# 6_ZynTra-Zynq-DDR_Interface.net
KiCad netlist of a schematic drawn in Altium Designer
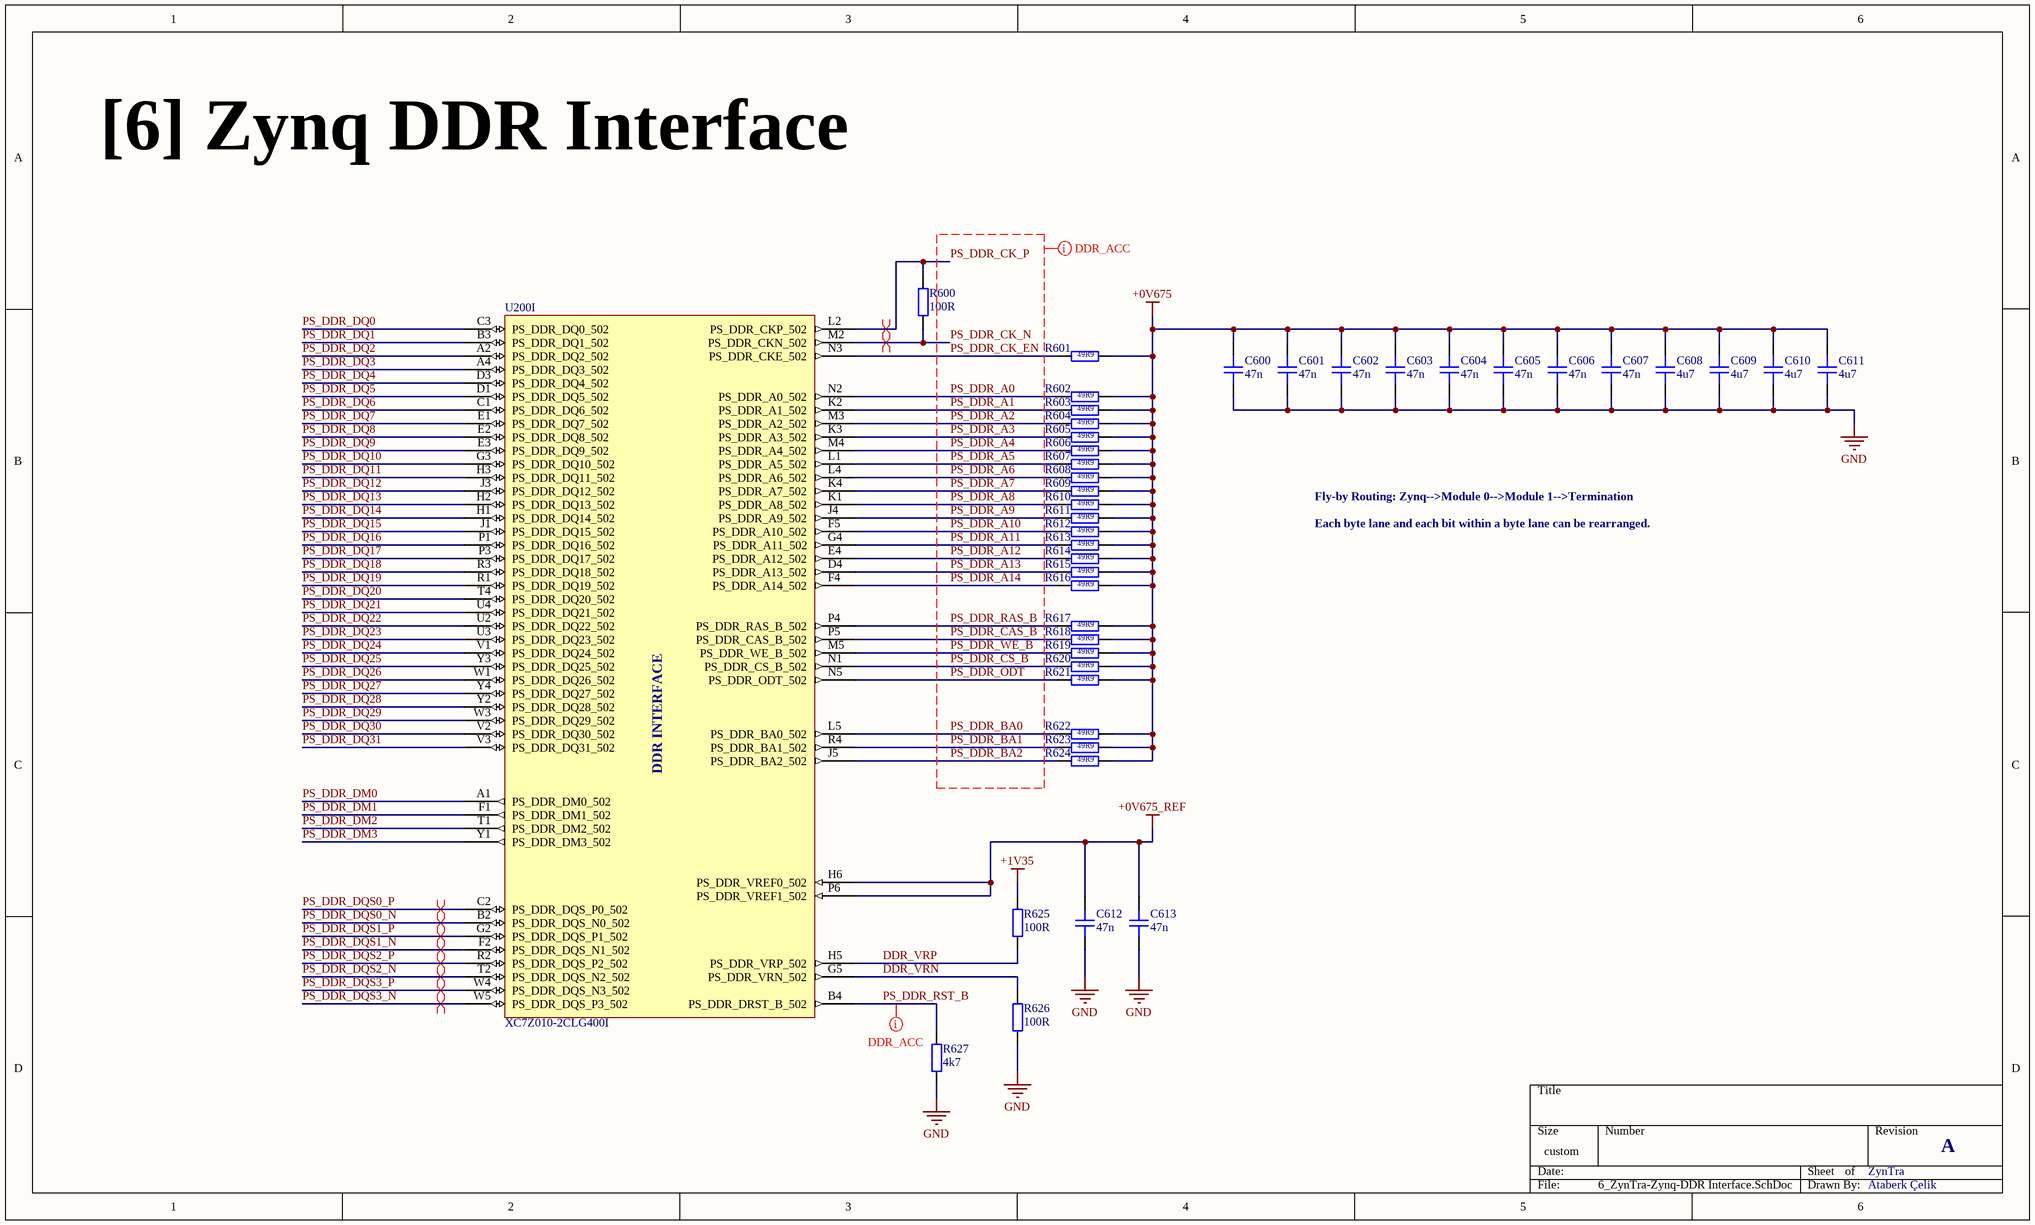
[diagram p0: 6_ZynTra-Zynq-DDR Interface.SchDoc]

(export (version "E")
  (design (tool "Eeschema 10.0.6"))
  (components
    (comp (ref "C600")
      (value "47n")
      (footprint "CAP_0201")
      (description "Capacitor SMD 0201")
      (libsource (lib "Schematic-Lib-PhilsLab") (part "CAP_0201"))
    )
    (comp (ref "C601")
      (value "47n")
      (footprint "CAP_0201")
      (description "Capacitor SMD 0201")
      (libsource (lib "Schematic-Lib-PhilsLab") (part "CAP_0201"))
    )
    (comp (ref "C602")
      (value "47n")
      (footprint "CAP_0201")
      (description "Capacitor SMD 0201")
      (libsource (lib "Schematic-Lib-PhilsLab") (part "CAP_0201"))
    )
    (comp (ref "C603")
      (value "47n")
      (footprint "CAP_0201")
      (description "Capacitor SMD 0201")
      (libsource (lib "Schematic-Lib-PhilsLab") (part "CAP_0201"))
    )
    (comp (ref "C604")
      (value "47n")
      (footprint "CAP_0201")
      (description "Capacitor SMD 0201")
      (libsource (lib "Schematic-Lib-PhilsLab") (part "CAP_0201"))
    )
    (comp (ref "C605")
      (value "47n")
      (footprint "CAP_0201")
      (description "Capacitor SMD 0201")
      (libsource (lib "Schematic-Lib-PhilsLab") (part "CAP_0201"))
    )
    (comp (ref "C606")
      (value "47n")
      (footprint "CAP_0201")
      (description "Capacitor SMD 0201")
      (libsource (lib "Schematic-Lib-PhilsLab") (part "CAP_0201"))
    )
    (comp (ref "C607")
      (value "47n")
      (footprint "CAP_0201")
      (description "Capacitor SMD 0201")
      (libsource (lib "Schematic-Lib-PhilsLab") (part "CAP_0201"))
    )
    (comp (ref "C608")
      (value "4u7")
      (footprint "CAP_0402")
      (description "Capacitor SMD 0402")
      (libsource (lib "Schematic-Lib-PhilsLab") (part "CAP_0402"))
    )
    (comp (ref "C609")
      (value "4u7")
      (footprint "CAP_0402")
      (description "Capacitor SMD 0402")
      (libsource (lib "Schematic-Lib-PhilsLab") (part "CAP_0402"))
    )
    (comp (ref "C610")
      (value "4u7")
      (footprint "CAP_0402")
      (description "Capacitor SMD 0402")
      (libsource (lib "Schematic-Lib-PhilsLab") (part "CAP_0402"))
    )
    (comp (ref "C611")
      (value "4u7")
      (footprint "CAP_0402")
      (description "Capacitor SMD 0402")
      (libsource (lib "Schematic-Lib-PhilsLab") (part "CAP_0402"))
    )
    (comp (ref "C612")
      (value "47n")
      (footprint "CAP_0201")
      (description "Capacitor SMD 0201")
      (libsource (lib "Schematic-Lib-PhilsLab") (part "CAP_0201"))
    )
    (comp (ref "C613")
      (value "47n")
      (footprint "CAP_0201")
      (description "Capacitor SMD 0201")
      (libsource (lib "Schematic-Lib-PhilsLab") (part "CAP_0201"))
    )
    (comp (ref "R600")
      (value "100R")
      (footprint "RES_0201")
      (description "Resistor SMD 0201")
      (libsource (lib "Schematic-Lib-PhilsLab") (part "RES_0201"))
    )
    (comp (ref "R601")
      (value "49R9")
      (footprint "RES_0201")
      (description "Resistor SMD 0201")
      (libsource (lib "Schematic-Lib-PhilsLab") (part "RES_0201"))
    )
    (comp (ref "R602")
      (value "49R9")
      (footprint "RES_0201")
      (description "Resistor SMD 0201")
      (libsource (lib "Schematic-Lib-PhilsLab") (part "RES_0201"))
    )
    (comp (ref "R603")
      (value "49R9")
      (footprint "RES_0201")
      (description "Resistor SMD 0201")
      (libsource (lib "Schematic-Lib-PhilsLab") (part "RES_0201"))
    )
    (comp (ref "R604")
      (value "49R9")
      (footprint "RES_0201")
      (description "Resistor SMD 0201")
      (libsource (lib "Schematic-Lib-PhilsLab") (part "RES_0201"))
    )
    (comp (ref "R605")
      (value "49R9")
      (footprint "RES_0201")
      (description "Resistor SMD 0201")
      (libsource (lib "Schematic-Lib-PhilsLab") (part "RES_0201"))
    )
    (comp (ref "R606")
      (value "49R9")
      (footprint "RES_0201")
      (description "Resistor SMD 0201")
      (libsource (lib "Schematic-Lib-PhilsLab") (part "RES_0201"))
    )
    (comp (ref "R607")
      (value "49R9")
      (footprint "RES_0201")
      (description "Resistor SMD 0201")
      (libsource (lib "Schematic-Lib-PhilsLab") (part "RES_0201"))
    )
    (comp (ref "R608")
      (value "49R9")
      (footprint "RES_0201")
      (description "Resistor SMD 0201")
      (libsource (lib "Schematic-Lib-PhilsLab") (part "RES_0201"))
    )
    (comp (ref "R609")
      (value "49R9")
      (footprint "RES_0201")
      (description "Resistor SMD 0201")
      (libsource (lib "Schematic-Lib-PhilsLab") (part "RES_0201"))
    )
    (comp (ref "R610")
      (value "49R9")
      (footprint "RES_0201")
      (description "Resistor SMD 0201")
      (libsource (lib "Schematic-Lib-PhilsLab") (part "RES_0201"))
    )
    (comp (ref "R611")
      (value "49R9")
      (footprint "RES_0201")
      (description "Resistor SMD 0201")
      (libsource (lib "Schematic-Lib-PhilsLab") (part "RES_0201"))
    )
    (comp (ref "R612")
      (value "49R9")
      (footprint "RES_0201")
      (description "Resistor SMD 0201")
      (libsource (lib "Schematic-Lib-PhilsLab") (part "RES_0201"))
    )
    (comp (ref "R613")
      (value "49R9")
      (footprint "RES_0201")
      (description "Resistor SMD 0201")
      (libsource (lib "Schematic-Lib-PhilsLab") (part "RES_0201"))
    )
    (comp (ref "R614")
      (value "49R9")
      (footprint "RES_0201")
      (description "Resistor SMD 0201")
      (libsource (lib "Schematic-Lib-PhilsLab") (part "RES_0201"))
    )
    (comp (ref "R615")
      (value "49R9")
      (footprint "RES_0201")
      (description "Resistor SMD 0201")
      (libsource (lib "Schematic-Lib-PhilsLab") (part "RES_0201"))
    )
    (comp (ref "R616")
      (value "49R9")
      (footprint "RES_0201")
      (description "Resistor SMD 0201")
      (libsource (lib "Schematic-Lib-PhilsLab") (part "RES_0201"))
    )
    (comp (ref "R617")
      (value "49R9")
      (footprint "RES_0201")
      (description "Resistor SMD 0201")
      (libsource (lib "Schematic-Lib-PhilsLab") (part "RES_0201"))
    )
    (comp (ref "R618")
      (value "49R9")
      (footprint "RES_0201")
      (description "Resistor SMD 0201")
      (libsource (lib "Schematic-Lib-PhilsLab") (part "RES_0201"))
    )
    (comp (ref "R619")
      (value "49R9")
      (footprint "RES_0201")
      (description "Resistor SMD 0201")
      (libsource (lib "Schematic-Lib-PhilsLab") (part "RES_0201"))
    )
    (comp (ref "R620")
      (value "49R9")
      (footprint "RES_0201")
      (description "Resistor SMD 0201")
      (libsource (lib "Schematic-Lib-PhilsLab") (part "RES_0201"))
    )
    (comp (ref "R621")
      (value "49R9")
      (footprint "RES_0201")
      (description "Resistor SMD 0201")
      (libsource (lib "Schematic-Lib-PhilsLab") (part "RES_0201"))
    )
    (comp (ref "R622")
      (value "49R9")
      (footprint "RES_0201")
      (description "Resistor SMD 0201")
      (libsource (lib "Schematic-Lib-PhilsLab") (part "RES_0201"))
    )
    (comp (ref "R623")
      (value "49R9")
      (footprint "RES_0201")
      (description "Resistor SMD 0201")
      (libsource (lib "Schematic-Lib-PhilsLab") (part "RES_0201"))
    )
    (comp (ref "R624")
      (value "49R9")
      (footprint "RES_0201")
      (description "Resistor SMD 0201")
      (libsource (lib "Schematic-Lib-PhilsLab") (part "RES_0201"))
    )
    (comp (ref "R625")
      (value "100R")
      (footprint "RES_0201")
      (description "Resistor SMD 0201")
      (libsource (lib "Schematic-Lib-PhilsLab") (part "RES_0201"))
    )
    (comp (ref "R626")
      (value "100R")
      (footprint "RES_0201")
      (description "Resistor SMD 0201")
      (libsource (lib "Schematic-Lib-PhilsLab") (part "RES_0201"))
    )
    (comp (ref "R627")
      (value "4k7")
      (footprint "RES_0201")
      (description "Resistor SMD 0201")
      (libsource (lib "Schematic-Lib-PhilsLab") (part "RES_0201"))
    )
    (comp (ref "U200")
      (value "XC7Z010-2CLG400I")
      (footprint "CLG400, 0.8mm, 17x17")
      (fields (field (name "MANUFACTURER") "AMD / Xilinx"))
      (libsource (lib "AtaSchLib") (part "XC7Z010-2CLG400I"))
    )
  )
  (nets
    (net (code "1") (name "+0V675") (class "Default")
      (node (ref "C600") (pin "2") (pinfunction "2_2") (pintype "passive"))
      (node (ref "C601") (pin "2") (pinfunction "2_2") (pintype "passive"))
      (node (ref "C602") (pin "2") (pinfunction "2_2") (pintype "passive"))
      (node (ref "C603") (pin "2") (pinfunction "2_2") (pintype "passive"))
      (node (ref "C604") (pin "2") (pinfunction "2_2") (pintype "passive"))
      (node (ref "C605") (pin "2") (pinfunction "2_2") (pintype "passive"))
      (node (ref "C606") (pin "2") (pinfunction "2_2") (pintype "passive"))
      (node (ref "C607") (pin "2") (pinfunction "2_2") (pintype "passive"))
      (node (ref "C608") (pin "2") (pinfunction "2_2") (pintype "passive"))
      (node (ref "C609") (pin "2") (pinfunction "2_2") (pintype "passive"))
      (node (ref "C610") (pin "2") (pinfunction "2_2") (pintype "passive"))
      (node (ref "C611") (pin "2") (pinfunction "2_2") (pintype "passive"))
      (node (ref "R601") (pin "2") (pinfunction "2_2") (pintype "passive"))
      (node (ref "R602") (pin "2") (pinfunction "2_2") (pintype "passive"))
      (node (ref "R603") (pin "2") (pinfunction "2_2") (pintype "passive"))
      (node (ref "R604") (pin "2") (pinfunction "2_2") (pintype "passive"))
      (node (ref "R605") (pin "2") (pinfunction "2_2") (pintype "passive"))
      (node (ref "R606") (pin "2") (pinfunction "2_2") (pintype "passive"))
      (node (ref "R607") (pin "2") (pinfunction "2_2") (pintype "passive"))
      (node (ref "R608") (pin "2") (pinfunction "2_2") (pintype "passive"))
      (node (ref "R609") (pin "2") (pinfunction "2_2") (pintype "passive"))
      (node (ref "R610") (pin "2") (pinfunction "2_2") (pintype "passive"))
      (node (ref "R611") (pin "2") (pinfunction "2_2") (pintype "passive"))
      (node (ref "R612") (pin "2") (pinfunction "2_2") (pintype "passive"))
      (node (ref "R613") (pin "2") (pinfunction "2_2") (pintype "passive"))
      (node (ref "R614") (pin "2") (pinfunction "2_2") (pintype "passive"))
      (node (ref "R615") (pin "2") (pinfunction "2_2") (pintype "passive"))
      (node (ref "R616") (pin "2") (pinfunction "2_2") (pintype "passive"))
      (node (ref "R617") (pin "2") (pinfunction "2_2") (pintype "passive"))
      (node (ref "R618") (pin "2") (pinfunction "2_2") (pintype "passive"))
      (node (ref "R619") (pin "2") (pinfunction "2_2") (pintype "passive"))
      (node (ref "R620") (pin "2") (pinfunction "2_2") (pintype "passive"))
      (node (ref "R621") (pin "2") (pinfunction "2_2") (pintype "passive"))
      (node (ref "R622") (pin "2") (pinfunction "2_2") (pintype "passive"))
      (node (ref "R623") (pin "2") (pinfunction "2_2") (pintype "passive"))
      (node (ref "R624") (pin "2") (pinfunction "2_2") (pintype "passive"))
    )
    (net (code "2") (name "+0V675_REF") (class "Default")
      (node (ref "C612") (pin "2") (pinfunction "2_2") (pintype "passive"))
      (node (ref "C613") (pin "2") (pinfunction "2_2") (pintype "passive"))
      (node (ref "U200") (pin "H6") (pinfunction "PS_DDR_VREF0_502_H6") (pintype "input"))
      (node (ref "U200") (pin "P6") (pinfunction "PS_DDR_VREF1_502_P6") (pintype "input"))
    )
    (net (code "3") (name "+1V35") (class "Default")
      (node (ref "R625") (pin "2") (pinfunction "2_2") (pintype "passive"))
    )
    (net (code "4") (name "/DDR_VRN") (class "Default")
      (node (ref "R626") (pin "2") (pinfunction "2_2") (pintype "passive"))
      (node (ref "U200") (pin "G5") (pinfunction "PS_DDR_VRN_502_G5") (pintype "output"))
    )
    (net (code "5") (name "/DDR_VRP") (class "Default")
      (node (ref "R625") (pin "1") (pinfunction "1_1") (pintype "passive"))
      (node (ref "U200") (pin "H5") (pinfunction "PS_DDR_VRP_502_H5") (pintype "output"))
    )
    (net (code "6") (name "/PS_DDR_A0") (class "Default")
      (node (ref "R602") (pin "1") (pinfunction "1_1") (pintype "passive"))
      (node (ref "U200") (pin "N2") (pinfunction "PS_DDR_A0_502_N2") (pintype "output"))
    )
    (net (code "7") (name "/PS_DDR_A1") (class "Default")
      (node (ref "R603") (pin "1") (pinfunction "1_1") (pintype "passive"))
      (node (ref "U200") (pin "K2") (pinfunction "PS_DDR_A1_502_K2") (pintype "output"))
    )
    (net (code "8") (name "/PS_DDR_A2") (class "Default")
      (node (ref "R604") (pin "1") (pinfunction "1_1") (pintype "passive"))
      (node (ref "U200") (pin "M3") (pinfunction "PS_DDR_A2_502_M3") (pintype "output"))
    )
    (net (code "9") (name "/PS_DDR_A3") (class "Default")
      (node (ref "R605") (pin "1") (pinfunction "1_1") (pintype "passive"))
      (node (ref "U200") (pin "K3") (pinfunction "PS_DDR_A3_502_K3") (pintype "output"))
    )
    (net (code "10") (name "/PS_DDR_A4") (class "Default")
      (node (ref "R606") (pin "1") (pinfunction "1_1") (pintype "passive"))
      (node (ref "U200") (pin "M4") (pinfunction "PS_DDR_A4_502_M4") (pintype "output"))
    )
    (net (code "11") (name "/PS_DDR_A5") (class "Default")
      (node (ref "R607") (pin "1") (pinfunction "1_1") (pintype "passive"))
      (node (ref "U200") (pin "L1") (pinfunction "PS_DDR_A5_502_L1") (pintype "output"))
    )
    (net (code "12") (name "/PS_DDR_A6") (class "Default")
      (node (ref "R608") (pin "1") (pinfunction "1_1") (pintype "passive"))
      (node (ref "U200") (pin "L4") (pinfunction "PS_DDR_A6_502_L4") (pintype "output"))
    )
    (net (code "13") (name "/PS_DDR_A7") (class "Default")
      (node (ref "R609") (pin "1") (pinfunction "1_1") (pintype "passive"))
      (node (ref "U200") (pin "K4") (pinfunction "PS_DDR_A7_502_K4") (pintype "output"))
    )
    (net (code "14") (name "/PS_DDR_A8") (class "Default")
      (node (ref "R610") (pin "1") (pinfunction "1_1") (pintype "passive"))
      (node (ref "U200") (pin "K1") (pinfunction "PS_DDR_A8_502_K1") (pintype "output"))
    )
    (net (code "15") (name "/PS_DDR_A9") (class "Default")
      (node (ref "R611") (pin "1") (pinfunction "1_1") (pintype "passive"))
      (node (ref "U200") (pin "J4") (pinfunction "PS_DDR_A9_502_J4") (pintype "output"))
    )
    (net (code "16") (name "/PS_DDR_A10") (class "Default")
      (node (ref "R612") (pin "1") (pinfunction "1_1") (pintype "passive"))
      (node (ref "U200") (pin "F5") (pinfunction "PS_DDR_A10_502_F5") (pintype "output"))
    )
    (net (code "17") (name "/PS_DDR_A11") (class "Default")
      (node (ref "R613") (pin "1") (pinfunction "1_1") (pintype "passive"))
      (node (ref "U200") (pin "G4") (pinfunction "PS_DDR_A11_502_G4") (pintype "output"))
    )
    (net (code "18") (name "/PS_DDR_A12") (class "Default")
      (node (ref "R614") (pin "1") (pinfunction "1_1") (pintype "passive"))
      (node (ref "U200") (pin "E4") (pinfunction "PS_DDR_A12_502_E4") (pintype "output"))
    )
    (net (code "19") (name "/PS_DDR_A13") (class "Default")
      (node (ref "R615") (pin "1") (pinfunction "1_1") (pintype "passive"))
      (node (ref "U200") (pin "D4") (pinfunction "PS_DDR_A13_502_D4") (pintype "output"))
    )
    (net (code "20") (name "/PS_DDR_A14") (class "Default")
      (node (ref "R616") (pin "1") (pinfunction "1_1") (pintype "passive"))
      (node (ref "U200") (pin "F4") (pinfunction "PS_DDR_A14_502_F4") (pintype "output"))
    )
    (net (code "21") (name "/PS_DDR_BA0") (class "Default")
      (node (ref "R622") (pin "1") (pinfunction "1_1") (pintype "passive"))
      (node (ref "U200") (pin "L5") (pinfunction "PS_DDR_BA0_502_L5") (pintype "output"))
    )
    (net (code "22") (name "/PS_DDR_BA1") (class "Default")
      (node (ref "R623") (pin "1") (pinfunction "1_1") (pintype "passive"))
      (node (ref "U200") (pin "R4") (pinfunction "PS_DDR_BA1_502_R4") (pintype "output"))
    )
    (net (code "23") (name "/PS_DDR_BA2") (class "Default")
      (node (ref "R624") (pin "1") (pinfunction "1_1") (pintype "passive"))
      (node (ref "U200") (pin "J5") (pinfunction "PS_DDR_BA2_502_J5") (pintype "output"))
    )
    (net (code "24") (name "/PS_DDR_CAS_B") (class "Default")
      (node (ref "R618") (pin "1") (pinfunction "1_1") (pintype "passive"))
      (node (ref "U200") (pin "P5") (pinfunction "PS_DDR_CAS_B_502_P5") (pintype "output"))
    )
    (net (code "25") (name "/PS_DDR_CK_EN") (class "Default")
      (node (ref "R601") (pin "1") (pinfunction "1_1") (pintype "passive"))
      (node (ref "U200") (pin "N3") (pinfunction "PS_DDR_CKE_502_N3") (pintype "output"))
    )
    (net (code "26") (name "/PS_DDR_CK_N") (class "Default")
      (node (ref "R600") (pin "1") (pinfunction "1_1") (pintype "passive"))
      (node (ref "U200") (pin "M2") (pinfunction "PS_DDR_CKN_502_M2") (pintype "output"))
    )
    (net (code "27") (name "/PS_DDR_CK_P") (class "Default")
      (node (ref "R600") (pin "2") (pinfunction "2_2") (pintype "passive"))
      (node (ref "U200") (pin "L2") (pinfunction "PS_DDR_CKP_502_L2") (pintype "output"))
    )
    (net (code "28") (name "/PS_DDR_CS_B") (class "Default")
      (node (ref "R620") (pin "1") (pinfunction "1_1") (pintype "passive"))
      (node (ref "U200") (pin "N1") (pinfunction "PS_DDR_CS_B_502_N1") (pintype "output"))
    )
    (net (code "29") (name "/PS_DDR_DM0") (class "Default")
      (node (ref "U200") (pin "A1") (pinfunction "PS_DDR_DM0_502_A1") (pintype "output"))
    )
    (net (code "30") (name "/PS_DDR_DM1") (class "Default")
      (node (ref "U200") (pin "F1") (pinfunction "PS_DDR_DM1_502_F1") (pintype "output"))
    )
    (net (code "31") (name "/PS_DDR_DM2") (class "Default")
      (node (ref "U200") (pin "T1") (pinfunction "PS_DDR_DM2_502_T1") (pintype "output"))
    )
    (net (code "32") (name "/PS_DDR_DM3") (class "Default")
      (node (ref "U200") (pin "Y1") (pinfunction "PS_DDR_DM3_502_Y1") (pintype "output"))
    )
    (net (code "33") (name "/PS_DDR_DQ0") (class "Default")
      (node (ref "U200") (pin "C3") (pinfunction "PS_DDR_DQ0_502_C3") (pintype "bidirectional"))
    )
    (net (code "34") (name "/PS_DDR_DQ1") (class "Default")
      (node (ref "U200") (pin "B3") (pinfunction "PS_DDR_DQ1_502_B3") (pintype "bidirectional"))
    )
    (net (code "35") (name "/PS_DDR_DQ2") (class "Default")
      (node (ref "U200") (pin "A2") (pinfunction "PS_DDR_DQ2_502_A2") (pintype "bidirectional"))
    )
    (net (code "36") (name "/PS_DDR_DQ3") (class "Default")
      (node (ref "U200") (pin "A4") (pinfunction "PS_DDR_DQ3_502_A4") (pintype "bidirectional"))
    )
    (net (code "37") (name "/PS_DDR_DQ4") (class "Default")
      (node (ref "U200") (pin "D3") (pinfunction "PS_DDR_DQ4_502_D3") (pintype "bidirectional"))
    )
    (net (code "38") (name "/PS_DDR_DQ5") (class "Default")
      (node (ref "U200") (pin "D1") (pinfunction "PS_DDR_DQ5_502_D1") (pintype "bidirectional"))
    )
    (net (code "39") (name "/PS_DDR_DQ6") (class "Default")
      (node (ref "U200") (pin "C1") (pinfunction "PS_DDR_DQ6_502_C1") (pintype "bidirectional"))
    )
    (net (code "40") (name "/PS_DDR_DQ7") (class "Default")
      (node (ref "U200") (pin "E1") (pinfunction "PS_DDR_DQ7_502_E1") (pintype "bidirectional"))
    )
    (net (code "41") (name "/PS_DDR_DQ8") (class "Default")
      (node (ref "U200") (pin "E2") (pinfunction "PS_DDR_DQ8_502_E2") (pintype "bidirectional"))
    )
    (net (code "42") (name "/PS_DDR_DQ9") (class "Default")
      (node (ref "U200") (pin "E3") (pinfunction "PS_DDR_DQ9_502_E3") (pintype "bidirectional"))
    )
    (net (code "43") (name "/PS_DDR_DQ10") (class "Default")
      (node (ref "U200") (pin "G3") (pinfunction "PS_DDR_DQ10_502_G3") (pintype "bidirectional"))
    )
    (net (code "44") (name "/PS_DDR_DQ11") (class "Default")
      (node (ref "U200") (pin "H3") (pinfunction "PS_DDR_DQ11_502_H3") (pintype "bidirectional"))
    )
    (net (code "45") (name "/PS_DDR_DQ12") (class "Default")
      (node (ref "U200") (pin "J3") (pinfunction "PS_DDR_DQ12_502_J3") (pintype "bidirectional"))
    )
    (net (code "46") (name "/PS_DDR_DQ13") (class "Default")
      (node (ref "U200") (pin "H2") (pinfunction "PS_DDR_DQ13_502_H2") (pintype "bidirectional"))
    )
    (net (code "47") (name "/PS_DDR_DQ14") (class "Default")
      (node (ref "U200") (pin "H1") (pinfunction "PS_DDR_DQ14_502_H1") (pintype "bidirectional"))
    )
    (net (code "48") (name "/PS_DDR_DQ15") (class "Default")
      (node (ref "U200") (pin "J1") (pinfunction "PS_DDR_DQ15_502_J1") (pintype "bidirectional"))
    )
    (net (code "49") (name "/PS_DDR_DQ16") (class "Default")
      (node (ref "U200") (pin "P1") (pinfunction "PS_DDR_DQ16_502_P1") (pintype "bidirectional"))
    )
    (net (code "50") (name "/PS_DDR_DQ17") (class "Default")
      (node (ref "U200") (pin "P3") (pinfunction "PS_DDR_DQ17_502_P3") (pintype "bidirectional"))
    )
    (net (code "51") (name "/PS_DDR_DQ18") (class "Default")
      (node (ref "U200") (pin "R3") (pinfunction "PS_DDR_DQ18_502_R3") (pintype "bidirectional"))
    )
    (net (code "52") (name "/PS_DDR_DQ19") (class "Default")
      (node (ref "U200") (pin "R1") (pinfunction "PS_DDR_DQ19_502_R1") (pintype "bidirectional"))
    )
    (net (code "53") (name "/PS_DDR_DQ20") (class "Default")
      (node (ref "U200") (pin "T4") (pinfunction "PS_DDR_DQ20_502_T4") (pintype "bidirectional"))
    )
    (net (code "54") (name "/PS_DDR_DQ21") (class "Default")
      (node (ref "U200") (pin "U4") (pinfunction "PS_DDR_DQ21_502_U4") (pintype "bidirectional"))
    )
    (net (code "55") (name "/PS_DDR_DQ22") (class "Default")
      (node (ref "U200") (pin "U2") (pinfunction "PS_DDR_DQ22_502_U2") (pintype "bidirectional"))
    )
    (net (code "56") (name "/PS_DDR_DQ23") (class "Default")
      (node (ref "U200") (pin "U3") (pinfunction "PS_DDR_DQ23_502_U3") (pintype "bidirectional"))
    )
    (net (code "57") (name "/PS_DDR_DQ24") (class "Default")
      (node (ref "U200") (pin "V1") (pinfunction "PS_DDR_DQ24_502_V1") (pintype "bidirectional"))
    )
    (net (code "58") (name "/PS_DDR_DQ25") (class "Default")
      (node (ref "U200") (pin "Y3") (pinfunction "PS_DDR_DQ25_502_Y3") (pintype "bidirectional"))
    )
    (net (code "59") (name "/PS_DDR_DQ26") (class "Default")
      (node (ref "U200") (pin "W1") (pinfunction "PS_DDR_DQ26_502_W1") (pintype "bidirectional"))
    )
    (net (code "60") (name "/PS_DDR_DQ27") (class "Default")
      (node (ref "U200") (pin "Y4") (pinfunction "PS_DDR_DQ27_502_Y4") (pintype "bidirectional"))
    )
    (net (code "61") (name "/PS_DDR_DQ28") (class "Default")
      (node (ref "U200") (pin "Y2") (pinfunction "PS_DDR_DQ28_502_Y2") (pintype "bidirectional"))
    )
    (net (code "62") (name "/PS_DDR_DQ29") (class "Default")
      (node (ref "U200") (pin "W3") (pinfunction "PS_DDR_DQ29_502_W3") (pintype "bidirectional"))
    )
    (net (code "63") (name "/PS_DDR_DQ30") (class "Default")
      (node (ref "U200") (pin "V2") (pinfunction "PS_DDR_DQ30_502_V2") (pintype "bidirectional"))
    )
    (net (code "64") (name "/PS_DDR_DQ31") (class "Default")
      (node (ref "U200") (pin "V3") (pinfunction "PS_DDR_DQ31_502_V3") (pintype "bidirectional"))
    )
    (net (code "65") (name "/PS_DDR_DQS0_N") (class "Default")
      (node (ref "U200") (pin "B2") (pinfunction "PS_DDR_DQS_N0_502_B2") (pintype "bidirectional"))
    )
    (net (code "66") (name "/PS_DDR_DQS0_P") (class "Default")
      (node (ref "U200") (pin "C2") (pinfunction "PS_DDR_DQS_P0_502_C2") (pintype "bidirectional"))
    )
    (net (code "67") (name "/PS_DDR_DQS1_N") (class "Default")
      (node (ref "U200") (pin "F2") (pinfunction "PS_DDR_DQS_N1_502_F2") (pintype "bidirectional"))
    )
    (net (code "68") (name "/PS_DDR_DQS1_P") (class "Default")
      (node (ref "U200") (pin "G2") (pinfunction "PS_DDR_DQS_P1_502_G2") (pintype "bidirectional"))
    )
    (net (code "69") (name "/PS_DDR_DQS2_N") (class "Default")
      (node (ref "U200") (pin "T2") (pinfunction "PS_DDR_DQS_N2_502_T2") (pintype "bidirectional"))
    )
    (net (code "70") (name "/PS_DDR_DQS2_P") (class "Default")
      (node (ref "U200") (pin "R2") (pinfunction "PS_DDR_DQS_P2_502_R2") (pintype "bidirectional"))
    )
    (net (code "71") (name "/PS_DDR_DQS3_N") (class "Default")
      (node (ref "U200") (pin "W5") (pinfunction "PS_DDR_DQS_P3_502_W5") (pintype "bidirectional"))
    )
    (net (code "72") (name "/PS_DDR_DQS3_P") (class "Default")
      (node (ref "U200") (pin "W4") (pinfunction "PS_DDR_DQS_N3_502_W4") (pintype "bidirectional"))
    )
    (net (code "73") (name "/PS_DDR_ODT") (class "Default")
      (node (ref "R621") (pin "1") (pinfunction "1_1") (pintype "passive"))
      (node (ref "U200") (pin "N5") (pinfunction "PS_DDR_ODT_502_N5") (pintype "output"))
    )
    (net (code "74") (name "/PS_DDR_RAS_B") (class "Default")
      (node (ref "R617") (pin "1") (pinfunction "1_1") (pintype "passive"))
      (node (ref "U200") (pin "P4") (pinfunction "PS_DDR_RAS_B_502_P4") (pintype "output"))
    )
    (net (code "75") (name "/PS_DDR_RST_B") (class "Default")
      (node (ref "R627") (pin "2") (pinfunction "2_2") (pintype "passive"))
      (node (ref "U200") (pin "B4") (pinfunction "PS_DDR_DRST_B_502_B4") (pintype "output"))
    )
    (net (code "76") (name "/PS_DDR_WE_B") (class "Default")
      (node (ref "R619") (pin "1") (pinfunction "1_1") (pintype "passive"))
      (node (ref "U200") (pin "M5") (pinfunction "PS_DDR_WE_B_502_M5") (pintype "output"))
    )
    (net (code "77") (name "GND") (class "Default")
      (node (ref "C600") (pin "1") (pinfunction "1_1") (pintype "passive"))
      (node (ref "C601") (pin "1") (pinfunction "1_1") (pintype "passive"))
      (node (ref "C602") (pin "1") (pinfunction "1_1") (pintype "passive"))
      (node (ref "C603") (pin "1") (pinfunction "1_1") (pintype "passive"))
      (node (ref "C604") (pin "1") (pinfunction "1_1") (pintype "passive"))
      (node (ref "C605") (pin "1") (pinfunction "1_1") (pintype "passive"))
      (node (ref "C606") (pin "1") (pinfunction "1_1") (pintype "passive"))
      (node (ref "C607") (pin "1") (pinfunction "1_1") (pintype "passive"))
      (node (ref "C608") (pin "1") (pinfunction "1_1") (pintype "passive"))
      (node (ref "C609") (pin "1") (pinfunction "1_1") (pintype "passive"))
      (node (ref "C610") (pin "1") (pinfunction "1_1") (pintype "passive"))
      (node (ref "C611") (pin "1") (pinfunction "1_1") (pintype "passive"))
      (node (ref "C612") (pin "1") (pinfunction "1_1") (pintype "passive"))
      (node (ref "C613") (pin "1") (pinfunction "1_1") (pintype "passive"))
      (node (ref "R626") (pin "1") (pinfunction "1_1") (pintype "passive"))
      (node (ref "R627") (pin "1") (pinfunction "1_1") (pintype "passive"))
    )
  )
)
